# PG01_Power_Supply.net
KiCad netlist of a schematic drawn in Altium Designer
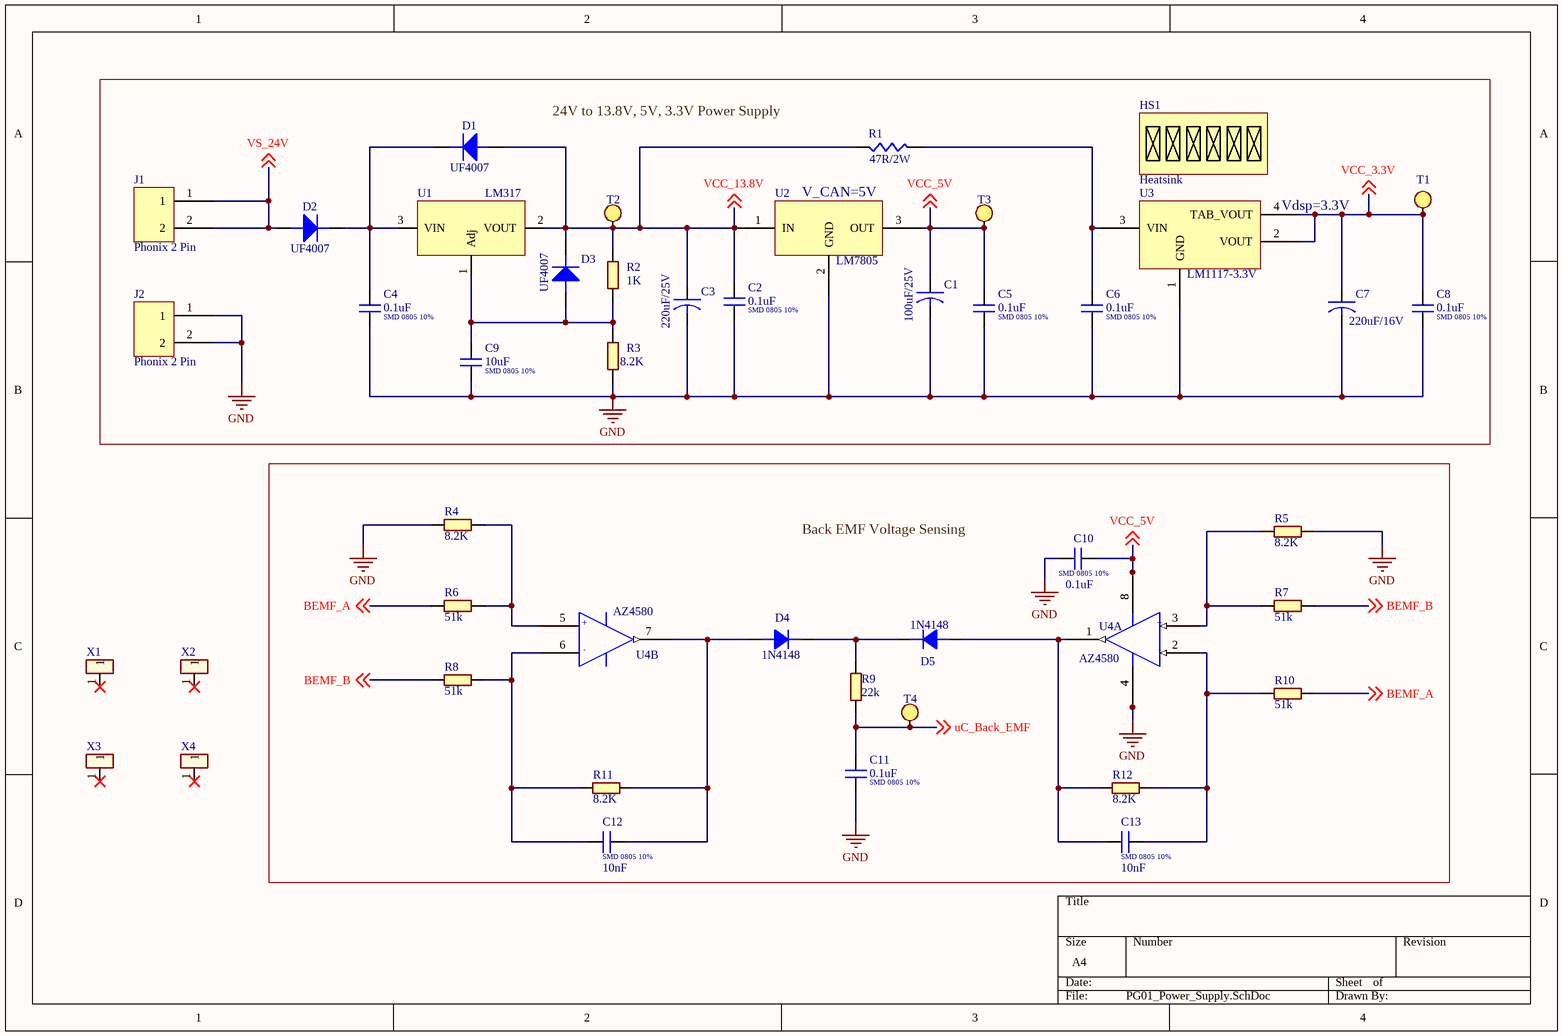
[diagram p0: PG01_Power_Supply.SchDoc]

(export (version "E")
  (design (tool "Eeschema 10.0.6"))
  (components
    (comp (ref "C1")
      (value "100uF/25V")
      (fields (field (name "Comment") "Electrolyte Cap"))
      (libsource (lib "*") (part "CAP"))
    )
    (comp (ref "C2")
      (value "SMD 0805 10%")
      (footprint "SMD0805")
      (fields (field (name "MANUFACTURER") "Vishay") (field (name "ALTIUM_VALUE") "0.1uF"))
      (libsource (lib "Schlib1") (part "CAP_SMD"))
    )
    (comp (ref "C3")
      (value "220uF/25V")
      (fields (field (name "Comment") "Electrolyte Cap"))
      (libsource (lib "*") (part "CAP"))
    )
    (comp (ref "C4")
      (value "SMD 0805 10%")
      (footprint "SMD0805")
      (fields (field (name "MANUFACTURER") "Vishay") (field (name "ALTIUM_VALUE") "0.1uF"))
      (libsource (lib "Schlib1") (part "CAP_SMD"))
    )
    (comp (ref "C5")
      (value "SMD 0805 10%")
      (footprint "SMD0805")
      (fields (field (name "MANUFACTURER") "Vishay") (field (name "ALTIUM_VALUE") "0.1uF"))
      (libsource (lib "Schlib1") (part "CAP_SMD"))
    )
    (comp (ref "C6")
      (value "SMD 0805 10%")
      (footprint "SMD0805")
      (fields (field (name "MANUFACTURER") "Vishay") (field (name "ALTIUM_VALUE") "0.1uF"))
      (libsource (lib "Schlib1") (part "CAP_SMD"))
    )
    (comp (ref "C7")
      (value "220uF/16V")
      (fields (field (name "Comment") "Electrolyte Cap"))
      (libsource (lib "*") (part "CAP"))
    )
    (comp (ref "C8")
      (value "SMD 0805 10%")
      (footprint "SMD0805")
      (fields (field (name "MANUFACTURER") "Vishay") (field (name "ALTIUM_VALUE") "0.1uF"))
      (libsource (lib "Schlib1") (part "CAP_SMD"))
    )
    (comp (ref "C9")
      (value "SMD 0805 10%")
      (footprint "SMD0805")
      (fields (field (name "MANUFACTURER") "Vishay") (field (name "ALTIUM_VALUE") "10uF"))
      (libsource (lib "Schlib1") (part "CAP_SMD"))
    )
    (comp (ref "C10")
      (value "SMD 0805 10%")
      (footprint "SMD0805")
      (fields (field (name "MANUFACTURER") "Vishay") (field (name "ALTIUM_VALUE") "0.1uF"))
      (libsource (lib "Schlib1") (part "CAP_SMD"))
    )
    (comp (ref "C11")
      (value "SMD 0805 10%")
      (footprint "SMD0805")
      (fields (field (name "MANUFACTURER") "Vishay") (field (name "ALTIUM_VALUE") "0.1uF"))
      (libsource (lib "Schlib1") (part "CAP_SMD"))
    )
    (comp (ref "C12")
      (value "SMD 0805 10%")
      (footprint "SMD0805")
      (fields (field (name "MANUFACTURER") "Vishay") (field (name "ALTIUM_VALUE") "10nF"))
      (libsource (lib "Schlib1") (part "CAP_SMD"))
    )
    (comp (ref "C13")
      (value "SMD 0805 10%")
      (footprint "SMD0805")
      (fields (field (name "MANUFACTURER") "Vishay") (field (name "ALTIUM_VALUE") "10nF"))
      (libsource (lib "Schlib1") (part "CAP_SMD"))
    )
    (comp (ref "D1")
      (value "UF4007")
      (footprint "DO-214(SMA)")
      (fields (field (name "MANUFACTURER") "Diodes Corp") (field (name "Comment") "Diode SMA"))
      (libsource (lib "Schlib1") (part "Diode_SMA"))
    )
    (comp (ref "D2")
      (value "UF4007")
      (footprint "DO-214(SMA)")
      (fields (field (name "MANUFACTURER") "Diodes Corp") (field (name "Comment") "Diode SMA"))
      (libsource (lib "Schlib1") (part "Diode_SMA"))
    )
    (comp (ref "D3")
      (value "UF4007")
      (footprint "DO-214(SMA)")
      (fields (field (name "MANUFACTURER") "Diodes Corp") (field (name "Comment") "Diode SMA"))
      (libsource (lib "Schlib1") (part "Diode_SMA"))
    )
    (comp (ref "D4")
      (value "1N4148")
      (fields
        (field (name "PART NO.") "SM4007")
        (field (name "TOLERANCE") "10%")
        (field (name "MANUFACTURER") "Vishay")
      )
      (libsource (lib "*") (part "1N4148"))
    )
    (comp (ref "D5")
      (value "1N4148")
      (fields
        (field (name "PART NO.") "SM4007")
        (field (name "TOLERANCE") "10%")
        (field (name "MANUFACTURER") "Vishay")
      )
      (libsource (lib "*") (part "1N4148"))
    )
    (comp (ref "HS1")
      (value "Heatsink")
      (footprint "Heatsink_25mm")
      (libsource (lib "Schlib1") (part "HS_15W"))
    )
    (comp (ref "J1")
      (value "Phonix 2 Pin")
      (footprint "PHONIX2")
      (libsource (lib "Schlib1") (part "Phonix_2_Pin"))
    )
    (comp (ref "J2")
      (value "Phonix 2 Pin")
      (footprint "PHONIX2")
      (libsource (lib "Schlib1") (part "Phonix_2_Pin"))
    )
    (comp (ref "R1")
      (value "47R/2W")
      (footprint "Axial_2W_Vert")
      (fields (field (name "Comment") "Series Resistor"))
      (libsource (lib "Schlib1") (part "RES_TH"))
    )
    (comp (ref "R2")
      (value "1K")
      (footprint "SMD1206")
      (description "SMD1206  1% Resistor")
      (fields (field (name "MANUFACTURER") "Vishay") (field (name "Comment") "SMD 1206 1%"))
      (libsource (lib "") (part "RES_SMD_2"))
    )
    (comp (ref "R3")
      (value "8.2K")
      (footprint "SMD1206")
      (description "SMD1206  1% Resistor")
      (fields (field (name "MANUFACTURER") "Vishay") (field (name "Comment") "SMD 1206 1%"))
      (libsource (lib "") (part "RES_SMD_2"))
    )
    (comp (ref "R4")
      (value "8.2K")
      (footprint "SMD1206")
      (description "SMD1206  1% Resistor")
      (fields (field (name "MANUFACTURER") "Vishay") (field (name "Comment") "SMD 1206 1%"))
      (libsource (lib "") (part "RES_SMD_1"))
    )
    (comp (ref "R5")
      (value "8.2K")
      (footprint "SMD1206")
      (description "SMD1206  1% Resistor")
      (fields (field (name "MANUFACTURER") "Vishay") (field (name "Comment") "SMD 1206 1%"))
      (libsource (lib "") (part "RES_SMD_1"))
    )
    (comp (ref "R6")
      (value "51k")
      (footprint "SMD1206")
      (description "SMD1206  1% Resistor")
      (fields (field (name "MANUFACTURER") "Vishay") (field (name "Comment") "SMD 1206 1%"))
      (libsource (lib "") (part "RES_SMD_1"))
    )
    (comp (ref "R7")
      (value "51k")
      (footprint "SMD1206")
      (description "SMD1206  1% Resistor")
      (fields (field (name "MANUFACTURER") "Vishay") (field (name "Comment") "SMD 1206 1%"))
      (libsource (lib "") (part "RES_SMD_1"))
    )
    (comp (ref "R8")
      (value "51k")
      (footprint "SMD1206")
      (description "SMD1206  1% Resistor")
      (fields (field (name "MANUFACTURER") "Vishay") (field (name "Comment") "SMD 1206 1%"))
      (libsource (lib "") (part "RES_SMD_1"))
    )
    (comp (ref "R9")
      (value "22k")
      (footprint "SMD1206")
      (description "SMD1206  1% Resistor")
      (fields (field (name "MANUFACTURER") "Vishay") (field (name "Comment") "SMD 1206 1%"))
      (libsource (lib "Schlib1") (part "RES_SMD"))
    )
    (comp (ref "R10")
      (value "51k")
      (footprint "SMD1206")
      (description "SMD1206  1% Resistor")
      (fields (field (name "MANUFACTURER") "Vishay") (field (name "Comment") "SMD 1206 1%"))
      (libsource (lib "") (part "RES_SMD_1"))
    )
    (comp (ref "R11")
      (value "8.2K")
      (footprint "SMD1206")
      (description "SMD1206  1% Resistor")
      (fields (field (name "MANUFACTURER") "Vishay") (field (name "Comment") "SMD 1206 1%"))
      (libsource (lib "") (part "RES_SMD_1"))
    )
    (comp (ref "R12")
      (value "8.2K")
      (footprint "SMD1206")
      (description "SMD1206  1% Resistor")
      (fields (field (name "MANUFACTURER") "Vishay") (field (name "Comment") "SMD 1206 1%"))
      (libsource (lib "") (part "RES_SMD_1"))
    )
    (comp (ref "T1")
      (value "Through hole TestPoint")
      (footprint "TP")
      (libsource (lib "Schlib1") (part "TestPoint_TH"))
    )
    (comp (ref "T2")
      (value "Through hole TestPoint")
      (footprint "TP")
      (libsource (lib "Schlib1") (part "TestPoint_TH"))
    )
    (comp (ref "T3")
      (value "Through hole TestPoint")
      (footprint "TP")
      (libsource (lib "Schlib1") (part "TestPoint_TH"))
    )
    (comp (ref "T4")
      (value "Through hole TestPoint")
      (footprint "TP")
      (libsource (lib "Schlib1") (part "TestPoint_TH"))
    )
    (comp (ref "U1") (value "LM317") (footprint "TO220_Normal") (libsource (lib "Schlib1") (part "LM317")))
    (comp (ref "U2") (value "LM7805") (footprint "TO220_Normal") (libsource (lib "Schlib1") (part "LM7805")))
    (comp (ref "U3")
      (value "LM1117-3.3V")
      (footprint "SOT-223")
      (fields (field (name "Comment") "3.3V Regulator"))
      (libsource (lib "Schlib1") (part "LM1117"))
    )
    (comp (ref "U4")
      (value "AZ4580")
      (footprint "SOIC-8")
      (fields (field (name "MANUFACTURER") "ST Semiconductor") (field (name "Comment") "LM358"))
      (libsource (lib "*") (part "LM358"))
    )
    (comp (ref "X1") (value "TP") (libsource (lib "*") (part "TEST POINT_0")))
    (comp (ref "X2") (value "TP") (libsource (lib "*") (part "TEST POINT_0")))
    (comp (ref "X3") (value "TP") (libsource (lib "*") (part "TEST POINT_0")))
    (comp (ref "X4") (value "TP") (libsource (lib "*") (part "TEST POINT_0")))
  )
  (nets
    (net (code "1") (name "BEMF_A") (class "Default")
      (node (ref "R10") (pin "1") (pinfunction "1_1") (pintype "passive"))
      (node (ref "R6") (pin "2") (pinfunction "2_2") (pintype "passive"))
    )
    (net (code "2") (name "BEMF_B") (class "Default")
      (node (ref "R7") (pin "1") (pinfunction "1_1") (pintype "passive"))
      (node (ref "R8") (pin "2") (pinfunction "2_2") (pintype "passive"))
    )
    (net (code "3") (name "GND") (class "Default")
      (node (ref "C1") (pin "2") (pinfunction "2_2") (pintype "passive"))
      (node (ref "C10") (pin "1") (pinfunction "1_1") (pintype "passive"))
      (node (ref "C11") (pin "2") (pinfunction "2_2") (pintype "passive"))
      (node (ref "C2") (pin "2") (pinfunction "2_2") (pintype "passive"))
      (node (ref "C3") (pin "2") (pinfunction "2_2") (pintype "passive"))
      (node (ref "C4") (pin "2") (pinfunction "2_2") (pintype "passive"))
      (node (ref "C5") (pin "2") (pinfunction "2_2") (pintype "passive"))
      (node (ref "C6") (pin "2") (pinfunction "2_2") (pintype "passive"))
      (node (ref "C7") (pin "2") (pinfunction "2_2") (pintype "passive"))
      (node (ref "C8") (pin "2") (pinfunction "2_2") (pintype "passive"))
      (node (ref "C9") (pin "2") (pinfunction "2_2") (pintype "passive"))
      (node (ref "J2") (pin "1") (pinfunction "1_1") (pintype "passive"))
      (node (ref "J2") (pin "2") (pinfunction "2_2") (pintype "passive"))
      (node (ref "R3") (pin "1") (pinfunction "1_1") (pintype "passive"))
      (node (ref "R4") (pin "2") (pinfunction "2_2") (pintype "passive"))
      (node (ref "R5") (pin "1") (pinfunction "1_1") (pintype "passive"))
      (node (ref "U2") (pin "2") (pinfunction "GND_2") (pintype "passive"))
      (node (ref "U3") (pin "1") (pinfunction "GND_1") (pintype "passive"))
      (node (ref "U4") (pin "4") (pinfunction "GND_4") (pintype "power_in"))
    )
    (net (code "4") (name "Net-(D4-ANODE)") (class "Default")
      (node (ref "C12") (pin "1") (pinfunction "1_1") (pintype "passive"))
      (node (ref "D4") (pin "1") (pinfunction "ANODE_1") (pintype "passive"))
      (node (ref "R11") (pin "1") (pinfunction "1_1") (pintype "passive"))
      (node (ref "U4") (pin "7") (pinfunction "OUT_7") (pintype "output"))
    )
    (net (code "5") (name "Net-(D4-CATHODE)") (class "Default")
      (node (ref "D4") (pin "2") (pinfunction "CATHODE_2") (pintype "passive"))
      (node (ref "D5") (pin "2") (pinfunction "CATHODE_2") (pintype "passive"))
      (node (ref "R9") (pin "1") (pinfunction "1_1") (pintype "passive"))
    )
    (net (code "6") (name "Net-(D5-ANODE)") (class "Default")
      (node (ref "C13") (pin "2") (pinfunction "2_2") (pintype "passive"))
      (node (ref "D5") (pin "1") (pinfunction "ANODE_1") (pintype "passive"))
      (node (ref "R12") (pin "2") (pinfunction "2_2") (pintype "passive"))
      (node (ref "U4") (pin "1") (pinfunction "OUT_1") (pintype "output"))
    )
    (net (code "7") (name "Net-(U1-Adj)") (class "Default")
      (node (ref "C9") (pin "1") (pinfunction "1_1") (pintype "passive"))
      (node (ref "D3") (pin "1") (pintype "passive"))
      (node (ref "R2") (pin "1") (pinfunction "1_1") (pintype "passive"))
      (node (ref "R3") (pin "2") (pinfunction "2_2") (pintype "passive"))
      (node (ref "U1") (pin "1") (pinfunction "Adj_1") (pintype "passive"))
    )
    (net (code "8") (name "Net-(U1-VIN)") (class "Default")
      (node (ref "C4") (pin "1") (pinfunction "1_1") (pintype "passive"))
      (node (ref "D1") (pin "2") (pintype "passive"))
      (node (ref "D2") (pin "2") (pintype "passive"))
      (node (ref "U1") (pin "3") (pinfunction "VIN_3") (pintype "passive"))
    )
    (net (code "9") (name "Net-(U3-VIN)") (class "Default")
      (node (ref "C6") (pin "1") (pinfunction "1_1") (pintype "passive"))
      (node (ref "R1") (pin "2") (pintype "passive"))
      (node (ref "U3") (pin "3") (pinfunction "VIN_3") (pintype "passive"))
    )
    (net (code "10") (name "Net-(U4A-+IN)") (class "Default")
      (node (ref "R5") (pin "2") (pinfunction "2_2") (pintype "passive"))
      (node (ref "R7") (pin "2") (pinfunction "2_2") (pintype "passive"))
      (node (ref "U4") (pin "3") (pinfunction "+IN_3") (pintype "input"))
    )
    (net (code "11") (name "Net-(U4A--IN)") (class "Default")
      (node (ref "C13") (pin "1") (pinfunction "1_1") (pintype "passive"))
      (node (ref "R10") (pin "2") (pinfunction "2_2") (pintype "passive"))
      (node (ref "R12") (pin "1") (pinfunction "1_1") (pintype "passive"))
      (node (ref "U4") (pin "2") (pinfunction "-IN_2") (pintype "input"))
    )
    (net (code "12") (name "Net-(U4B-+IN)") (class "Default")
      (node (ref "R4") (pin "1") (pinfunction "1_1") (pintype "passive"))
      (node (ref "R6") (pin "1") (pinfunction "1_1") (pintype "passive"))
      (node (ref "U4") (pin "5") (pinfunction "+IN_5") (pintype "passive"))
    )
    (net (code "13") (name "Net-(U4B--IN)") (class "Default")
      (node (ref "C12") (pin "2") (pinfunction "2_2") (pintype "passive"))
      (node (ref "R11") (pin "2") (pinfunction "2_2") (pintype "passive"))
      (node (ref "R8") (pin "1") (pinfunction "1_1") (pintype "passive"))
      (node (ref "U4") (pin "6") (pinfunction "-IN_6") (pintype "passive"))
    )
    (net (code "14") (name "VCC_3.3V") (class "Default")
      (node (ref "C7") (pin "1") (pinfunction "1_1") (pintype "passive"))
      (node (ref "C8") (pin "1") (pinfunction "1_1") (pintype "passive"))
      (node (ref "T1") (pin "1") (pintype "passive"))
      (node (ref "U3") (pin "2") (pinfunction "VOUT_2") (pintype "passive"))
      (node (ref "U3") (pin "4") (pinfunction "TAB_VOUT_4") (pintype "passive"))
    )
    (net (code "15") (name "VCC_5V") (class "Default")
      (node (ref "C1") (pin "1") (pinfunction "1_1") (pintype "passive"))
      (node (ref "C10") (pin "2") (pinfunction "2_2") (pintype "passive"))
      (node (ref "C5") (pin "1") (pinfunction "1_1") (pintype "passive"))
      (node (ref "T3") (pin "1") (pintype "passive"))
      (node (ref "U2") (pin "3") (pinfunction "OUT_3") (pintype "passive"))
      (node (ref "U4") (pin "8") (pinfunction "VCC_8") (pintype "power_in"))
    )
    (net (code "16") (name "VCC_13.8V") (class "Default")
      (node (ref "C2") (pin "1") (pinfunction "1_1") (pintype "passive"))
      (node (ref "C3") (pin "1") (pinfunction "1_1") (pintype "passive"))
      (node (ref "D1") (pin "1") (pintype "passive"))
      (node (ref "D3") (pin "2") (pintype "passive"))
      (node (ref "R1") (pin "1") (pintype "passive"))
      (node (ref "R2") (pin "2") (pinfunction "2_2") (pintype "passive"))
      (node (ref "T2") (pin "1") (pintype "passive"))
      (node (ref "U1") (pin "2") (pinfunction "VOUT_2") (pintype "passive"))
      (node (ref "U2") (pin "1") (pinfunction "IN_1") (pintype "passive"))
    )
    (net (code "17") (name "VS_24V") (class "Default")
      (node (ref "D2") (pin "1") (pintype "passive"))
      (node (ref "J1") (pin "1") (pinfunction "1_1") (pintype "passive"))
      (node (ref "J1") (pin "2") (pinfunction "2_2") (pintype "passive"))
    )
    (net (code "18") (name "uC_Back_EMF") (class "Default")
      (node (ref "C11") (pin "1") (pinfunction "1_1") (pintype "passive"))
      (node (ref "R9") (pin "2") (pinfunction "2_2") (pintype "passive"))
      (node (ref "T4") (pin "1") (pintype "passive"))
    )
    (net (code "19") (name "unconnected-(X1-Pad1)") (class "Default")
      (node (ref "X1") (pin "1") (pinfunction "1_1") (pintype "passive+no_connect"))
    )
    (net (code "20") (name "unconnected-(X2-Pad1)") (class "Default")
      (node (ref "X2") (pin "1") (pinfunction "1_1") (pintype "passive+no_connect"))
    )
    (net (code "21") (name "unconnected-(X3-Pad1)") (class "Default")
      (node (ref "X3") (pin "1") (pinfunction "1_1") (pintype "passive+no_connect"))
    )
    (net (code "22") (name "unconnected-(X4-Pad1)") (class "Default")
      (node (ref "X4") (pin "1") (pinfunction "1_1") (pintype "passive+no_connect"))
    )
  )
)
